# LT1301_1.net
KiCad netlist of a schematic drawn in EAGLE
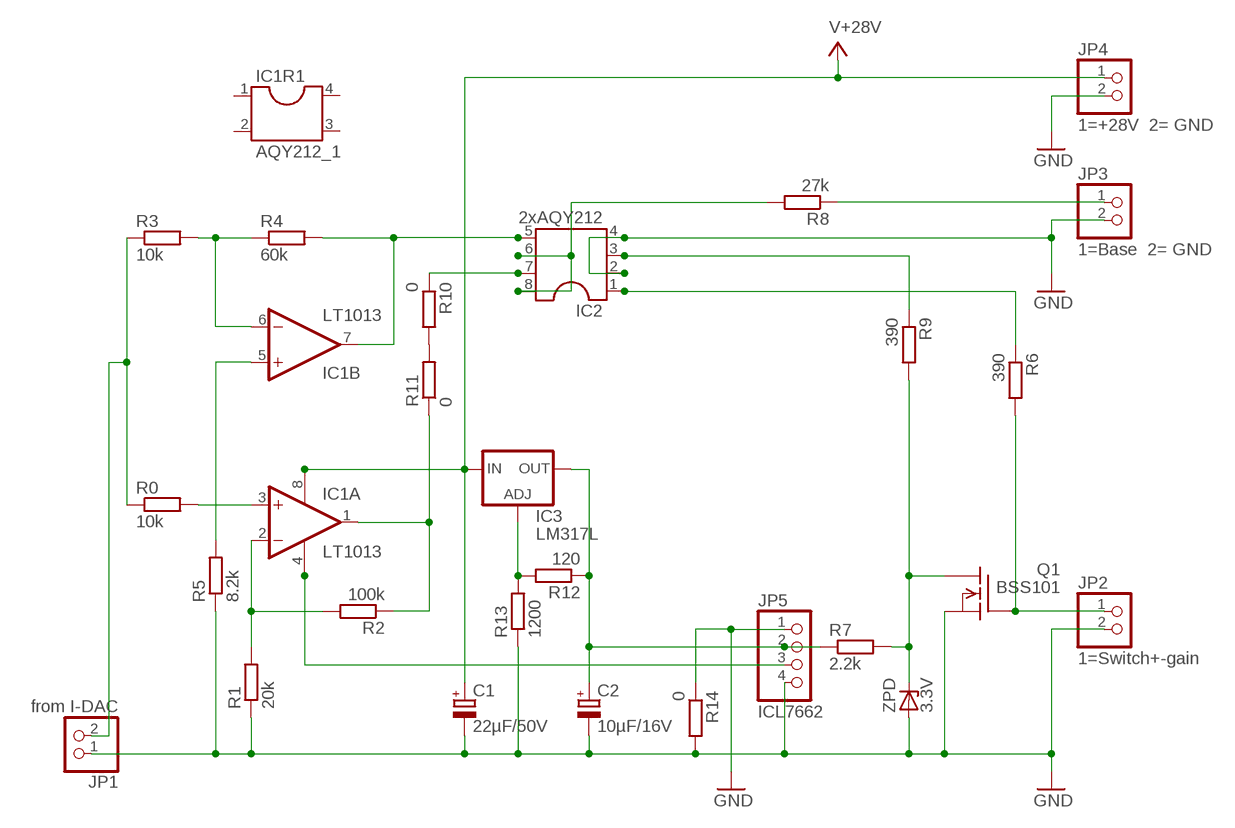
[diagram p0: schematic, sheet 1]

(export (version "E")
  (design (tool "Eeschema 10.0.6"))
  (components
    (comp (ref "C1")
      (value "22µF/50V")
      (footprint "eagle-import:E5-10,5")
      (libsource (lib "eagle-import") (part "CPOL-EUE5-10.5"))
    )
    (comp (ref "C2")
      (value "10µF/16V")
      (footprint "eagle-import:B45181B")
      (libsource (lib "eagle-import") (part "resistor_348_CPOL-EUB45181B"))
    )
    (comp (ref "IC1")
      (value "LT1013")
      (footprint "eagle-import:DIL08")
      (libsource (lib "eagle-import") (part "LF412N"))
    )
    (comp (ref "IC1R1")
      (value "AQY212_1")
      (footprint "eagle-import:SOCKET-04")
      (libsource (lib "eagle-import") (part "DIL4S"))
    )
    (comp (ref "IC2")
      (value "2xAQY212")
      (footprint "eagle-import:SOCKET-08")
      (libsource (lib "eagle-import") (part "DIL8S"))
    )
    (comp (ref "IC3")
      (value "LM317L")
      (footprint "eagle-import:317L")
      (libsource (lib "eagle-import") (part "LM317L"))
    )
    (comp (ref "JP1")
      (value "from I-DAC")
      (footprint "eagle-import:1X02")
      (libsource (lib "eagle-import") (part "PINHD-1X2"))
    )
    (comp (ref "JP2")
      (value "1=Switch+-gain")
      (footprint "eagle-import:1X02")
      (libsource (lib "eagle-import") (part "PINHD-1X2"))
    )
    (comp (ref "JP3")
      (value "1=Base 2= GND")
      (footprint "eagle-import:1X02")
      (libsource (lib "eagle-import") (part "PINHD-1X2"))
    )
    (comp (ref "JP4")
      (value "1=+28V 2= GND")
      (footprint "eagle-import:1X02")
      (libsource (lib "eagle-import") (part "PINHD-1X2"))
    )
    (comp (ref "JP5")
      (value "ICL7662")
      (footprint "eagle-import:1X04")
      (libsource (lib "eagle-import") (part "PINHD-1X4"))
    )
    (comp (ref "Q1")
      (value "BSS101")
      (footprint "eagle-import:TO92")
      (libsource (lib "eagle-import") (part "BSS101"))
    )
    (comp (ref "R0")
      (value "10k")
      (footprint "eagle-import:0207_7")
      (libsource (lib "eagle-import") (part "R-EU_0207/7"))
    )
    (comp (ref "R1")
      (value "20k")
      (footprint "eagle-import:0207_7")
      (libsource (lib "eagle-import") (part "R-EU_0207/7"))
    )
    (comp (ref "R2")
      (value "100k")
      (footprint "eagle-import:0207_7")
      (libsource (lib "eagle-import") (part "R-EU_0207/7"))
    )
    (comp (ref "R3")
      (value "10k")
      (footprint "eagle-import:0207_7")
      (libsource (lib "eagle-import") (part "R-EU_0207/7"))
    )
    (comp (ref "R4")
      (value "60k")
      (footprint "eagle-import:0207_7")
      (libsource (lib "eagle-import") (part "R-EU_0207/7"))
    )
    (comp (ref "R5")
      (value "8.2k")
      (footprint "eagle-import:0207_7")
      (libsource (lib "eagle-import") (part "R-EU_0207/7"))
    )
    (comp (ref "R6")
      (value "390")
      (footprint "eagle-import:0207_7")
      (libsource (lib "eagle-import") (part "R-EU_0207/7"))
    )
    (comp (ref "R7")
      (value "2.2k")
      (footprint "eagle-import:0207_7")
      (libsource (lib "eagle-import") (part "R-EU_0207/7"))
    )
    (comp (ref "R8")
      (value "27k")
      (footprint "eagle-import:0207_7")
      (libsource (lib "eagle-import") (part "R-EU_0207/7"))
    )
    (comp (ref "R9")
      (value "390")
      (footprint "eagle-import:0207_7")
      (libsource (lib "eagle-import") (part "R-EU_0207/7"))
    )
    (comp (ref "R10")
      (value "0")
      (footprint "eagle-import:0207_7")
      (libsource (lib "eagle-import") (part "R-EU_0207/7"))
    )
    (comp (ref "R11")
      (value "0")
      (footprint "eagle-import:0207_7")
      (libsource (lib "eagle-import") (part "R-EU_0207/7"))
    )
    (comp (ref "R12")
      (value "120")
      (footprint "eagle-import:0207_7")
      (libsource (lib "eagle-import") (part "R-EU_0207/7"))
    )
    (comp (ref "R13")
      (value "1200")
      (footprint "eagle-import:0207_7")
      (libsource (lib "eagle-import") (part "R-EU_0207/7"))
    )
    (comp (ref "R14")
      (value "0")
      (footprint "eagle-import:0207_7")
      (libsource (lib "eagle-import") (part "R-EU_0207/7"))
    )
    (comp (ref "ZPD")
      (value "3.3V")
      (footprint "eagle-import:ZDIO-7.5")
      (libsource (lib "eagle-import") (part "ZENER-DIODEZD-7.5"))
    )
  )
  (nets
    (net (code "1") (name "GND") (class "Default")
      (node (ref "C1") (pin "-") (pinfunction "-_-") (pintype "passive"))
      (node (ref "C2") (pin "-") (pinfunction "-_-") (pintype "passive"))
      (node (ref "IC2") (pin "2") (pinfunction "2_2") (pintype "passive"))
      (node (ref "IC2") (pin "4") (pinfunction "4_4") (pintype "passive"))
      (node (ref "JP1") (pin "1") (pinfunction "1_1") (pintype "passive"))
      (node (ref "JP2") (pin "2") (pinfunction "2_2") (pintype "passive"))
      (node (ref "JP3") (pin "2") (pinfunction "2_2") (pintype "passive"))
      (node (ref "JP4") (pin "2") (pinfunction "2_2") (pintype "passive"))
      (node (ref "JP5") (pin "1") (pinfunction "1_1") (pintype "passive"))
      (node (ref "JP5") (pin "4") (pinfunction "4_4") (pintype "passive"))
      (node (ref "Q1") (pin "1") (pinfunction "S_1") (pintype "passive"))
      (node (ref "R1") (pin "1") (pinfunction "1_1") (pintype "passive"))
      (node (ref "R13") (pin "1") (pinfunction "1_1") (pintype "passive"))
      (node (ref "R14") (pin "1") (pinfunction "1_1") (pintype "passive"))
      (node (ref "R14") (pin "2") (pinfunction "2_2") (pintype "passive"))
      (node (ref "R5") (pin "1") (pinfunction "1_1") (pintype "passive"))
      (node (ref "ZPD") (pin "A") (pinfunction "A_A") (pintype "passive"))
    )
    (net (code "2") (name "Net-(IC1A-+IN)") (class "Default")
      (node (ref "IC1") (pin "3") (pinfunction "+IN_3") (pintype "input"))
      (node (ref "R0") (pin "2") (pinfunction "2_2") (pintype "passive"))
    )
    (net (code "3") (name "Net-(IC1A--IN)") (class "Default")
      (node (ref "IC1") (pin "2") (pinfunction "-IN_2") (pintype "input"))
      (node (ref "R1") (pin "2") (pinfunction "2_2") (pintype "passive"))
      (node (ref "R2") (pin "2") (pinfunction "2_2") (pintype "passive"))
    )
    (net (code "4") (name "Net-(IC1A-OUT)") (class "Default")
      (node (ref "IC1") (pin "1") (pinfunction "OUT_1") (pintype "output"))
      (node (ref "R11") (pin "1") (pinfunction "1_1") (pintype "passive"))
      (node (ref "R2") (pin "1") (pinfunction "1_1") (pintype "passive"))
    )
    (net (code "5") (name "Net-(IC1B-+IN)") (class "Default")
      (node (ref "IC1") (pin "5") (pinfunction "+IN_5") (pintype "input"))
      (node (ref "R5") (pin "2") (pinfunction "2_2") (pintype "passive"))
    )
    (net (code "6") (name "Net-(IC1B--IN)") (class "Default")
      (node (ref "IC1") (pin "6") (pinfunction "-IN_6") (pintype "input"))
      (node (ref "R3") (pin "2") (pinfunction "2_2") (pintype "passive"))
      (node (ref "R4") (pin "1") (pinfunction "1_1") (pintype "passive"))
    )
    (net (code "7") (name "Net-(IC1B-OUT)") (class "Default")
      (node (ref "IC1") (pin "7") (pinfunction "OUT_7") (pintype "output"))
      (node (ref "IC2") (pin "5") (pinfunction "5_5") (pintype "passive"))
      (node (ref "R4") (pin "2") (pinfunction "2_2") (pintype "passive"))
    )
    (net (code "8") (name "Net-(IC1C-V-)") (class "Default")
      (node (ref "IC1") (pin "4") (pinfunction "V-_4") (pintype "power_in"))
      (node (ref "JP5") (pin "3") (pinfunction "3_3") (pintype "passive"))
    )
    (net (code "9") (name "Net-(IC2-Pad1)") (class "Default")
      (node (ref "IC2") (pin "1") (pinfunction "1_1") (pintype "passive"))
      (node (ref "R6") (pin "1") (pinfunction "1_1") (pintype "passive"))
    )
    (net (code "10") (name "Net-(IC2-Pad3)") (class "Default")
      (node (ref "IC2") (pin "3") (pinfunction "3_3") (pintype "passive"))
      (node (ref "R9") (pin "1") (pinfunction "1_1") (pintype "passive"))
    )
    (net (code "11") (name "Net-(IC2-Pad6)") (class "Default")
      (node (ref "IC2") (pin "6") (pinfunction "6_6") (pintype "passive"))
      (node (ref "IC2") (pin "8") (pinfunction "8_8") (pintype "passive"))
      (node (ref "R8") (pin "2") (pinfunction "2_2") (pintype "passive"))
    )
    (net (code "12") (name "Net-(IC2-Pad7)") (class "Default")
      (node (ref "IC2") (pin "7") (pinfunction "7_7") (pintype "passive"))
      (node (ref "R10") (pin "1") (pinfunction "1_1") (pintype "passive"))
    )
    (net (code "13") (name "Net-(IC3-ADJ)") (class "Default")
      (node (ref "IC3") (pin "1") (pinfunction "ADJ_1") (pintype "input"))
      (node (ref "R12") (pin "2") (pinfunction "2_2") (pintype "passive"))
      (node (ref "R13") (pin "2") (pinfunction "2_2") (pintype "passive"))
    )
    (net (code "14") (name "Net-(IC3-OUT)") (class "Default")
      (node (ref "C2") (pin "+") (pinfunction "+_+") (pintype "passive"))
      (node (ref "IC3") (pin "2") (pinfunction "OUT_2") (pintype "passive"))
      (node (ref "JP5") (pin "2") (pinfunction "2_2") (pintype "passive"))
      (node (ref "R12") (pin "1") (pinfunction "1_1") (pintype "passive"))
      (node (ref "R7") (pin "1") (pinfunction "1_1") (pintype "passive"))
    )
    (net (code "15") (name "Net-(JP1-Pad2)") (class "Default")
      (node (ref "JP1") (pin "2") (pinfunction "2_2") (pintype "passive"))
      (node (ref "R0") (pin "1") (pinfunction "1_1") (pintype "passive"))
      (node (ref "R3") (pin "1") (pinfunction "1_1") (pintype "passive"))
    )
    (net (code "16") (name "Net-(JP3-Pad1)") (class "Default")
      (node (ref "JP3") (pin "1") (pinfunction "1_1") (pintype "passive"))
      (node (ref "R8") (pin "1") (pinfunction "1_1") (pintype "passive"))
    )
    (net (code "17") (name "Net-(Q1-D)") (class "Default")
      (node (ref "Q1") (pin "3") (pinfunction "D_3") (pintype "passive"))
      (node (ref "R7") (pin "2") (pinfunction "2_2") (pintype "passive"))
      (node (ref "R9") (pin "2") (pinfunction "2_2") (pintype "passive"))
      (node (ref "ZPD") (pin "C") (pinfunction "C_C") (pintype "passive"))
    )
    (net (code "18") (name "Net-(Q1-G)") (class "Default")
      (node (ref "JP2") (pin "1") (pinfunction "1_1") (pintype "passive"))
      (node (ref "Q1") (pin "2") (pinfunction "G_2") (pintype "passive"))
      (node (ref "R6") (pin "2") (pinfunction "2_2") (pintype "passive"))
    )
    (net (code "19") (name "Net-(R10-Pad2)") (class "Default")
      (node (ref "R10") (pin "2") (pinfunction "2_2") (pintype "passive"))
      (node (ref "R11") (pin "2") (pinfunction "2_2") (pintype "passive"))
    )
    (net (code "20") (name "V+28V") (class "Default")
      (node (ref "C1") (pin "+") (pinfunction "+_+") (pintype "passive"))
      (node (ref "IC1") (pin "8") (pinfunction "V+_8") (pintype "power_in"))
      (node (ref "IC3") (pin "3") (pinfunction "IN_3") (pintype "input"))
      (node (ref "JP4") (pin "1") (pinfunction "1_1") (pintype "passive"))
    )
    (net (code "21") (name "unconnected-(IC1R1-Pad1)") (class "Default")
      (node (ref "IC1R1") (pin "1") (pinfunction "1_1") (pintype "passive"))
    )
    (net (code "22") (name "unconnected-(IC1R1-Pad2)") (class "Default")
      (node (ref "IC1R1") (pin "2") (pinfunction "2_2") (pintype "passive"))
    )
    (net (code "23") (name "unconnected-(IC1R1-Pad3)") (class "Default")
      (node (ref "IC1R1") (pin "3") (pinfunction "3_3") (pintype "passive"))
    )
    (net (code "24") (name "unconnected-(IC1R1-Pad4)") (class "Default")
      (node (ref "IC1R1") (pin "4") (pinfunction "4_4") (pintype "passive"))
    )
  )
)
